# Sheet2.net
KiCad netlist of a schematic drawn in Altium Designer
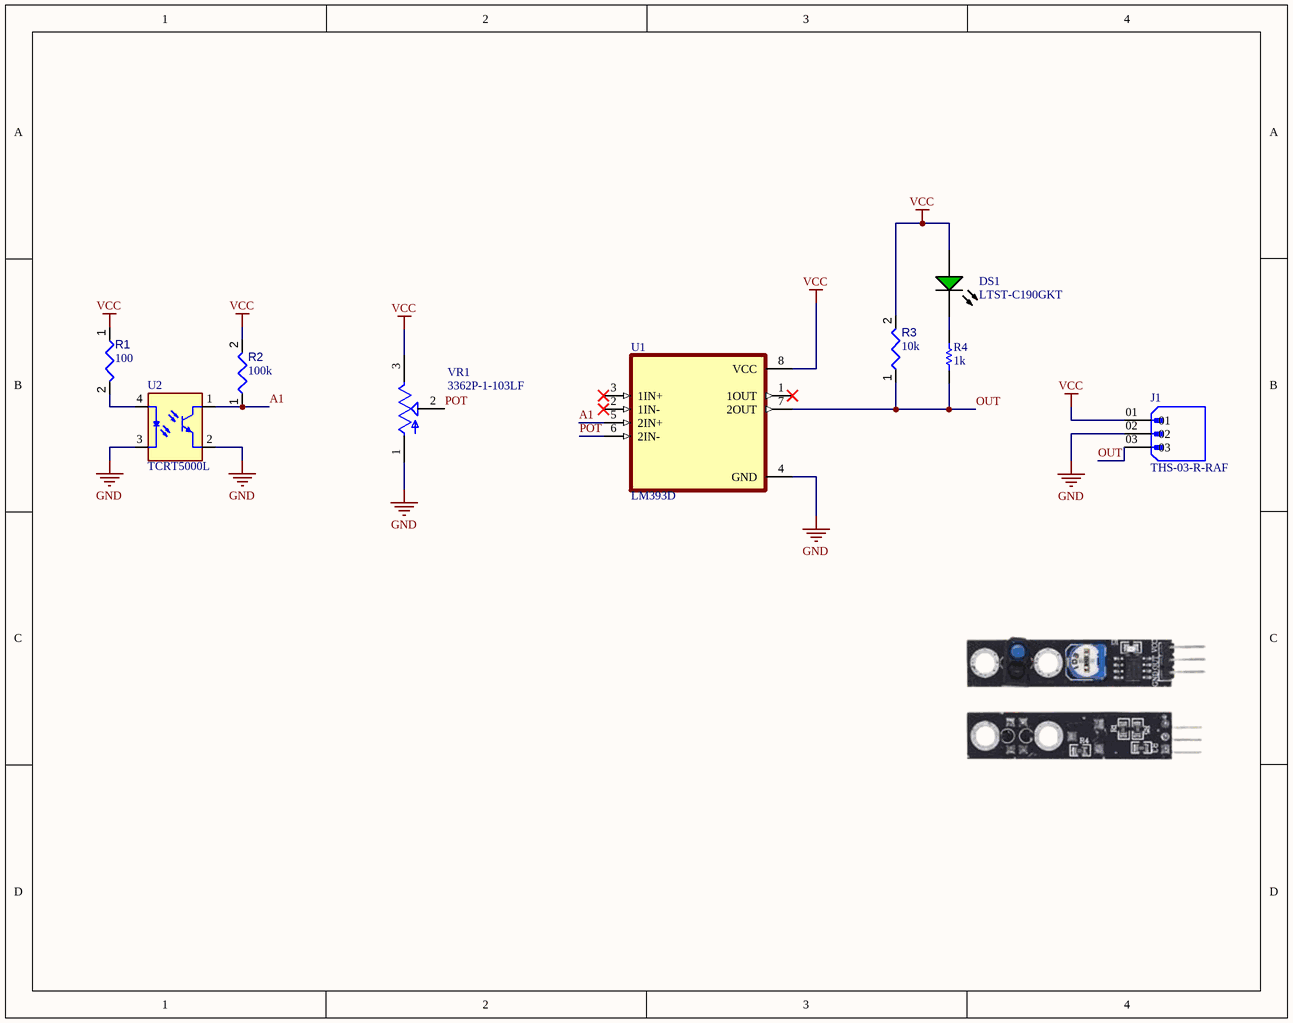
[diagram p0: Sheet2.SchDoc]

(export (version "E")
  (design (tool "Eeschema 10.0.6"))
  (components
    (comp (ref "DS1")
      (value "LTST-C190GKT")
      (footprint "LTST-C190GKT_V")
      (description "LED Uni-Color Green, 100 mW, 30 mA, -55 to 85 degC, 2-Pin SMD, RoHS, Tape and Reel")
      (fields (field (name "POWER") "100mW") (field (name "MANUFACTURER") "Lite-On"))
      (libsource (lib "Med khalil khlifi") (part "LED-GREEN-AK-2"))
    )
    (comp (ref "J1")
      (value "THS-03-R-RAF")
      (footprint "VALCON_THS-03-R-RAF")
      (libsource (lib "Header 3") (part "THS-03-R-RAF"))
    )
    (comp (ref "R1")
      (value "100")
      (footprint "RESC0402(1005)_L")
      (description "Chip Resistor, 100 Ohms, +/-1 %, 63 mW, -55 to 155 degC, 0402")
      (fields (field (name "POWER") "63mW") (field (name "TOLERANCE") "1%"))
      (libsource (lib "Med khalil khlifi") (part "RES-2"))
    )
    (comp (ref "R2")
      (value "100k")
      (footprint "RESC1005X40X25ML05T05")
      (description "Chip Resistor, 100 KOhm, +/- 1%, 0.063 W, -55 to 155 degC, 0402 (1005 Metric)")
      (fields (field (name "TOLERANCE") "1%") (field (name "POWER") "63mW"))
      (libsource (lib "Med khalil khlifi") (part "RES-2"))
    )
    (comp (ref "R3")
      (value "10k")
      (footprint "RESC1608X55X25ML10T15")
      (description "Chip Resistor, 10 KOhm, +/- 1%, 01 W, -55 to 155 degC, 0603 (1608 Metric)")
      (fields (field (name "POWER") "100mW") (field (name "TOLERANCE") "1%"))
      (libsource (lib "Med khalil khlifi") (part "RES-2"))
    )
    (comp (ref "R4")
      (value "1k")
      (footprint "RESC1005X40X25ML05T05")
      (description "Chip Resistor, 1 KOhm, +/- 1%, 0.1 W, -55 to 155 degC, 0402 (1005 Metric)")
      (fields (field (name "POWER") "100mW") (field (name "TOLERANCE") "1%"))
      (libsource (lib "") (part "RES-2_1"))
    )
    (comp (ref "U1")
      (value "LM393D")
      (footprint "SOIC127P599X175-8N")
      (description "Dual differential comparator, commercial grade")
      (fields (field (name "MF") "Texas Instruments"))
      (libsource (lib "LM393D") (part "LM393D"))
    )
    (comp (ref "U2")
      (value "TCRT5000L")
      (footprint "XDCR_TCRT5000L")
      (description "Reflective Optical Sensor 0.591 _15mm_ PCB Mount")
      (fields (field (name "MF") "Vishay"))
      (libsource (lib "TCRT5000L") (part "TCRT5000L"))
    )
    (comp (ref "VR1")
      (value "3362P-1-103LF")
      (footprint "TRIM_3362P-1-103LF")
      (description "10 kOhms 0.5W, 1/2W PC Pins Through Hole Trimmer Potentiometer Cermet 1 Turn Top Adjustment")
      (fields (field (name "DIGI-KEY_PART_NUMBER") "3362P-103LF-ND") (field (name "MF") "Bourns"))
      (libsource (lib "Potentiometer") (part "3362P-1-103LF"))
    )
  )
  (nets
    (net (code "1") (name "/A1") (class "Default")
      (node (ref "R2") (pin "1") (pinfunction "1_1") (pintype "passive"))
      (node (ref "U1") (pin "5") (pinfunction "2IN+_5") (pintype "input"))
      (node (ref "U2") (pin "1") (pinfunction "CO_1") (pintype "passive"))
    )
    (net (code "2") (name "/OUT") (class "Default")
      (node (ref "J1") (pin "03") (pinfunction "03_03") (pintype "passive"))
      (node (ref "R3") (pin "1") (pinfunction "1_1") (pintype "passive"))
      (node (ref "R4") (pin "1") (pinfunction "1_1") (pintype "passive"))
      (node (ref "U1") (pin "7") (pinfunction "2OUT_7") (pintype "output"))
    )
    (net (code "3") (name "/POT") (class "Default")
      (node (ref "U1") (pin "6") (pinfunction "2IN-_6") (pintype "input"))
      (node (ref "VR1") (pin "2") (pinfunction "WIPER_2") (pintype "passive"))
    )
    (net (code "4") (name "GND") (class "Default")
      (node (ref "J1") (pin "02") (pinfunction "02_02") (pintype "passive"))
      (node (ref "U1") (pin "4") (pinfunction "GND_4") (pintype "power_in"))
      (node (ref "U2") (pin "2") (pinfunction "E_2") (pintype "passive"))
      (node (ref "U2") (pin "3") (pinfunction "C_3") (pintype "passive"))
      (node (ref "VR1") (pin "1") (pinfunction "CCW_1") (pintype "passive"))
    )
    (net (code "5") (name "Net-(DS1-K)") (class "Default")
      (node (ref "DS1") (pin "2") (pinfunction "K_2") (pintype "passive"))
      (node (ref "R4") (pin "2") (pinfunction "2_2") (pintype "passive"))
    )
    (net (code "6") (name "Net-(U2-A)") (class "Default")
      (node (ref "R1") (pin "2") (pinfunction "2_2") (pintype "passive"))
      (node (ref "U2") (pin "4") (pinfunction "A_4") (pintype "passive"))
    )
    (net (code "7") (name "VCC") (class "Default")
      (node (ref "DS1") (pin "1") (pinfunction "A_1") (pintype "passive"))
      (node (ref "J1") (pin "01") (pinfunction "01_01") (pintype "passive"))
      (node (ref "R1") (pin "1") (pinfunction "1_1") (pintype "passive"))
      (node (ref "R2") (pin "2") (pinfunction "2_2") (pintype "passive"))
      (node (ref "R3") (pin "2") (pinfunction "2_2") (pintype "passive"))
      (node (ref "U1") (pin "8") (pinfunction "VCC_8") (pintype "power_in"))
      (node (ref "VR1") (pin "3") (pinfunction "CW_3") (pintype "passive"))
    )
    (net (code "8") (name "unconnected-(U1-1IN+-Pad3)") (class "Default")
      (node (ref "U1") (pin "3") (pinfunction "1IN+_3") (pintype "input+no_connect"))
    )
    (net (code "9") (name "unconnected-(U1-1IN--Pad2)") (class "Default")
      (node (ref "U1") (pin "2") (pinfunction "1IN-_2") (pintype "input+no_connect"))
    )
    (net (code "10") (name "unconnected-(U1-1OUT-Pad1)") (class "Default")
      (node (ref "U1") (pin "1") (pinfunction "1OUT_1") (pintype "output+no_connect"))
    )
  )
)
